# 09-IMC.net
KiCad netlist of a schematic drawn in Altium Designer
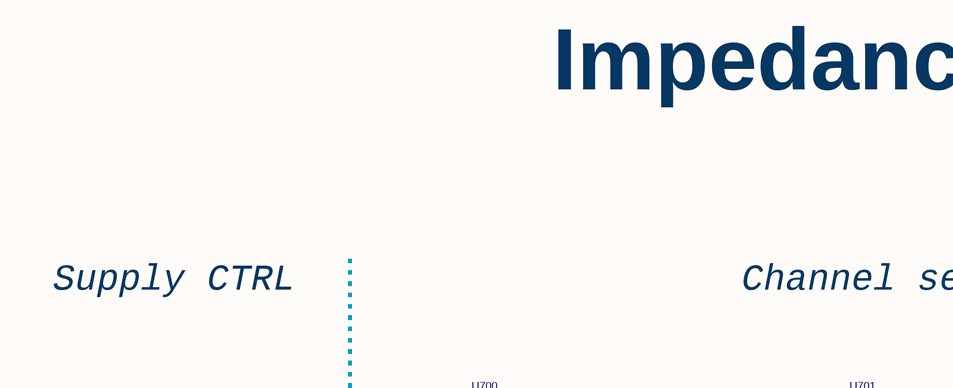
[diagram p0: 09-IMC.SchDoc, top left]
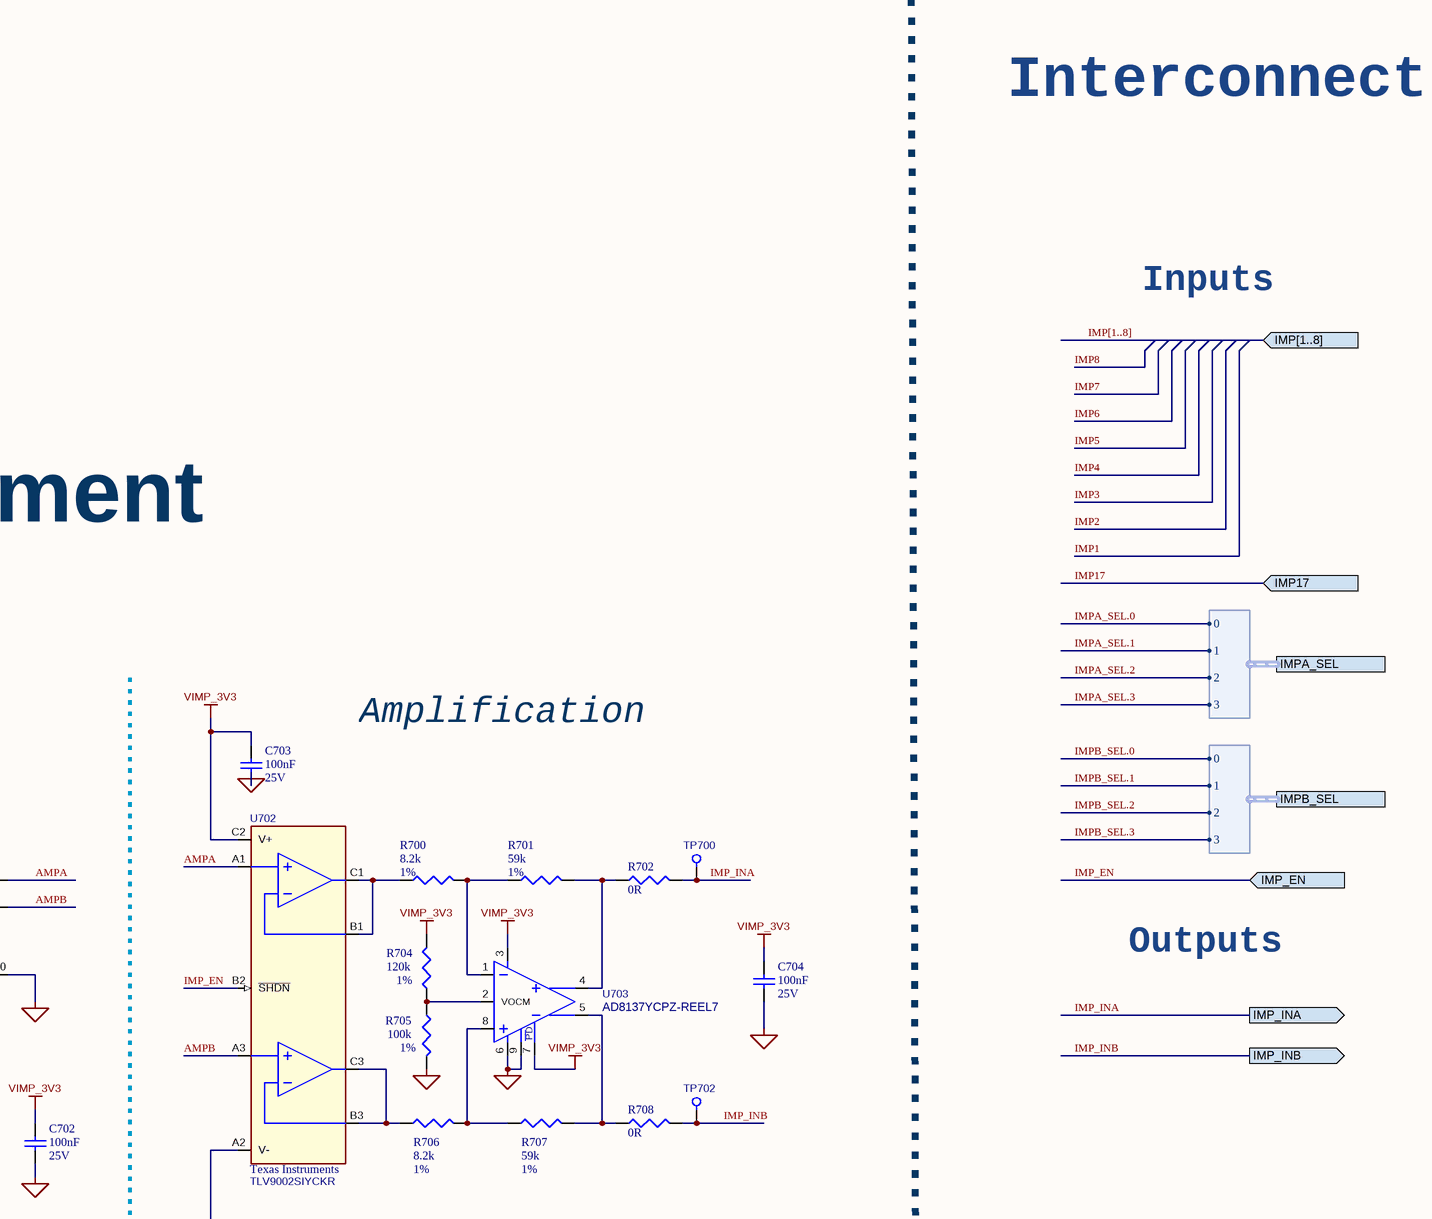
[diagram p1: 09-IMC.SchDoc, top right]
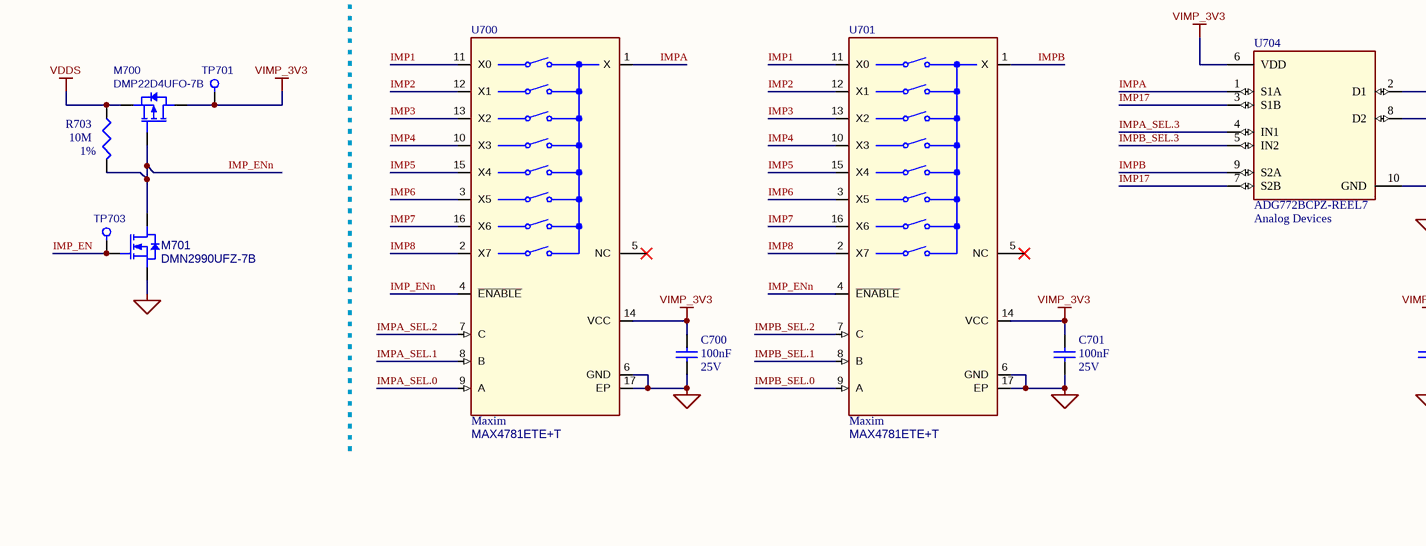
[diagram p2: 09-IMC.SchDoc, bottom left]
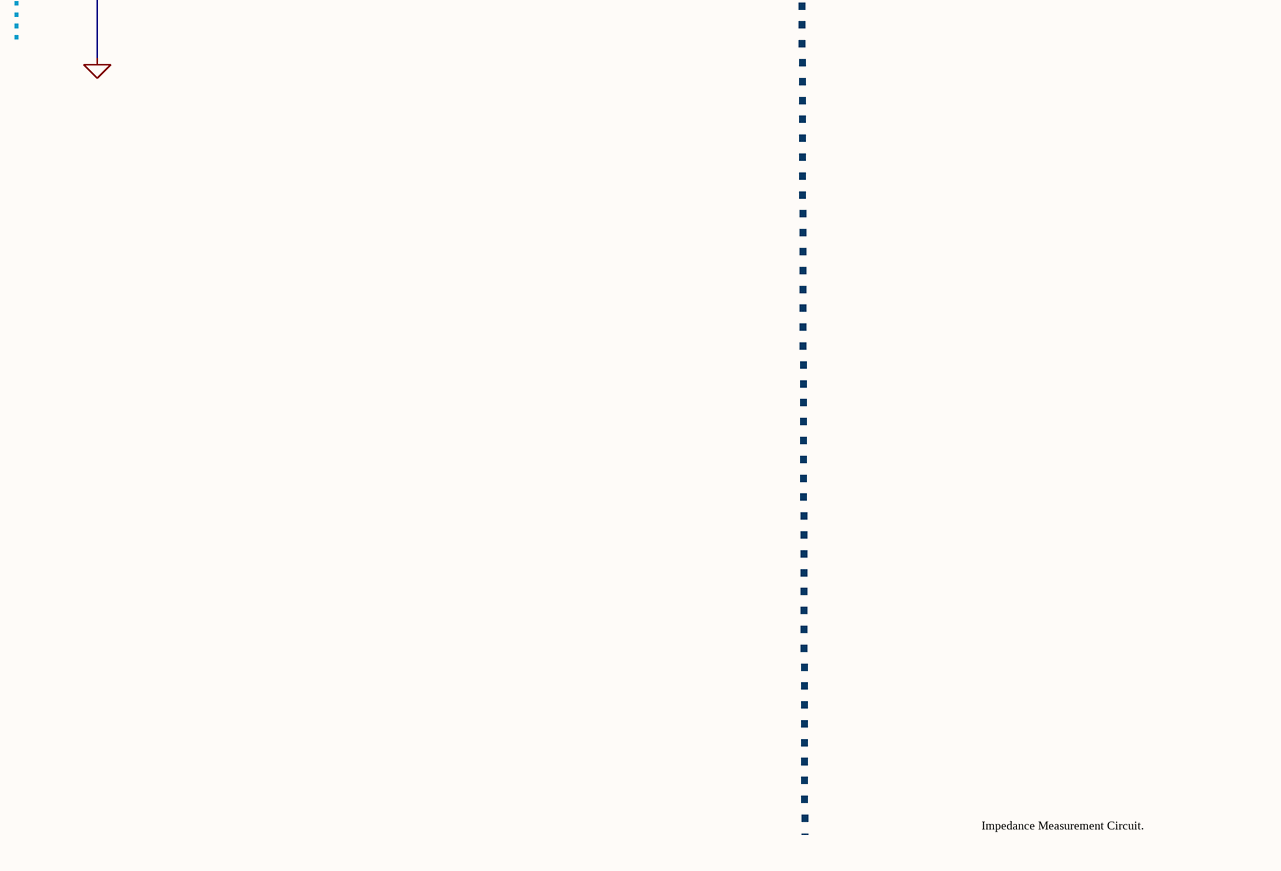
[diagram p3: 09-IMC.SchDoc, bottom right]

(export (version "E")
  (design (tool "Eeschema 10.0.6"))
  (components
    (comp (ref "C700")
      (value "100nF")
      (footprint "C0201_C")
      (fields
        (field (name "MANUFACTURER") "Murata")
        (field (name "MANUFACTURER PART NUMBER") "GRM033R61E104KE14J")
        (field (name "RATED DC VOLTAGE (URDC)") "25V")
      )
      (libsource (lib "MP-LIBRARY") (part "GRM033R61E104KE14J"))
    )
    (comp (ref "C701")
      (value "100nF")
      (footprint "C0201_C")
      (fields
        (field (name "MANUFACTURER") "Murata")
        (field (name "MANUFACTURER PART NUMBER") "GRM033R61E104KE14J")
        (field (name "RATED DC VOLTAGE (URDC)") "25V")
      )
      (libsource (lib "MP-LIBRARY") (part "GRM033R61E104KE14J"))
    )
    (comp (ref "C702")
      (value "100nF")
      (footprint "C0201_C")
      (fields
        (field (name "MANUFACTURER") "Murata")
        (field (name "MANUFACTURER PART NUMBER") "GRM033R61E104KE14J")
        (field (name "RATED DC VOLTAGE (URDC)") "25V")
      )
      (libsource (lib "MP-LIBRARY") (part "GRM033R61E104KE14J"))
    )
    (comp (ref "C703")
      (value "100nF")
      (footprint "C0201_C")
      (fields
        (field (name "MANUFACTURER") "Murata")
        (field (name "MANUFACTURER PART NUMBER") "GRM033R61E104KE14J")
        (field (name "RATED DC VOLTAGE (URDC)") "25V")
      )
      (libsource (lib "MP-LIBRARY") (part "GRM033R61E104KE14J"))
    )
    (comp (ref "C704")
      (value "100nF")
      (footprint "C0201_C")
      (fields
        (field (name "MANUFACTURER") "Murata")
        (field (name "MANUFACTURER PART NUMBER") "GRM033R61E104KE14J")
        (field (name "RATED DC VOLTAGE (URDC)") "25V")
      )
      (libsource (lib "MP-LIBRARY") (part "GRM033R61E104KE14J"))
    )
    (comp (ref "M700")
      (value "DMP22D4UFO-7B")
      (footprint "DIODESINC_X2-DFN0604-3")
      (description "MOSFET, P-chan, -20V, -383mA, DFN0604")
      (fields (field (name "MANUFACTURER") "Diodes Inc"))
      (libsource (lib "MP-LIBRARY") (part "DMP22D4UFO-7B"))
    )
    (comp (ref "M701")
      (value "DMN2990UFZ-7B")
      (footprint "DIODESINC_X2-DFN0606-3")
      (description "MOSFET, N-Chan, 20V, 170mA, DFN0606")
      (fields (field (name "MANUFACTURER") "Diodes Inc"))
      (libsource (lib "MP-LIBRARY") (part "DMN2990UFZ-7B"))
    )
    (comp (ref "R700")
      (value "8.2k")
      (footprint "R0201_C")
      (fields
        (field (name "MANUFACTURER") "Vishay")
        (field (name "MANUFACTURER PART NUMBER") "CRCW02018K20FNED")
        (field (name "TOLERANCE") "1%")
        (field (name "POWER") "50mW")
      )
      (libsource (lib "MP-LIBRARY") (part "CRCW02018K20FNED"))
    )
    (comp (ref "R701")
      (value "59k")
      (footprint "R0201_C")
      (fields
        (field (name "MANUFACTURER") "Vishay")
        (field (name "MANUFACTURER PART NUMBER") "CRCW020159K0FNED")
        (field (name "TOLERANCE") "1%")
        (field (name "POWER") "50mW")
      )
      (libsource (lib "MP-LIBRARY") (part "CRCW020159K0FNED"))
    )
    (comp (ref "R702")
      (value "0R")
      (footprint "R0201_C")
      (description "Fixed Resistor, Metal Glaze/thick Film, 0.05W, 0ohm, Surface Mount, 0201")
      (fields
        (field (name "MANUFACTURER") "Vishay")
        (field (name "MANUFACTURER PART NUMBER") "CRCW02010000Z0ED")
      )
      (libsource (lib "MP-LIBRARY") (part "CRCW02010000Z0ED"))
    )
    (comp (ref "R703")
      (value "10M")
      (footprint "R0201_C")
      (fields
        (field (name "MANUFACTURER") "Vishay Draloric")
        (field (name "MANUFACTURER PART NUMBER") "CRCW020110M0FNED")
        (field (name "TOLERANCE") "1%")
        (field (name "POWER") "50mW")
      )
      (libsource (lib "MP-LIBRARY") (part "CRCW020110M0FNED"))
    )
    (comp (ref "R704")
      (value "120k")
      (footprint "R0201_C")
      (fields
        (field (name "MANUFACTURER") "Vishay Dale")
        (field (name "MANUFACTURER PART NUMBER") "CRCW0201120KFNED")
        (field (name "TOLERANCE") "1%")
        (field (name "POWER") "50mW")
      )
      (libsource (lib "MP-LIBRARY") (part "CRCW0201120KFNED"))
    )
    (comp (ref "R705")
      (value "100k")
      (footprint "R0201_C")
      (fields
        (field (name "MANUFACTURER") "Vishay")
        (field (name "MANUFACTURER PART NUMBER") "CRCW0201100KFNED")
        (field (name "TOLERANCE") "1%")
        (field (name "POWER") "50mW")
      )
      (libsource (lib "MP-LIBRARY") (part "CRCW0201100KFNED"))
    )
    (comp (ref "R706")
      (value "8.2k")
      (footprint "R0201_C")
      (fields
        (field (name "MANUFACTURER") "Vishay")
        (field (name "MANUFACTURER PART NUMBER") "CRCW02018K20FNED")
        (field (name "TOLERANCE") "1%")
        (field (name "POWER") "50mW")
      )
      (libsource (lib "MP-LIBRARY") (part "CRCW02018K20FNED"))
    )
    (comp (ref "R707")
      (value "59k")
      (footprint "R0201_C")
      (fields
        (field (name "MANUFACTURER") "Vishay")
        (field (name "MANUFACTURER PART NUMBER") "CRCW020159K0FNED")
        (field (name "TOLERANCE") "1%")
        (field (name "POWER") "50mW")
      )
      (libsource (lib "MP-LIBRARY") (part "CRCW020159K0FNED"))
    )
    (comp (ref "R708")
      (value "0R")
      (footprint "R0201_C")
      (description "Fixed Resistor, Metal Glaze/thick Film, 0.05W, 0ohm, Surface Mount, 0201")
      (fields
        (field (name "MANUFACTURER") "Vishay")
        (field (name "MANUFACTURER PART NUMBER") "CRCW02010000Z0ED")
      )
      (libsource (lib "MP-LIBRARY") (part "CRCW02010000Z0ED"))
    )
    (comp (ref "TP700")
      (value "Test Point")
      (footprint "testpad_0.9mm")
      (description "Test pad, 0.90mm circular pad")
      (libsource (lib "MP-LIBRARY") (part "Test Point"))
    )
    (comp (ref "TP701")
      (value "Test Point")
      (footprint "testpad_0.9mm")
      (description "Test pad, 0.90mm circular pad")
      (libsource (lib "MP-LIBRARY") (part "Test Point"))
    )
    (comp (ref "TP702")
      (value "Test Point")
      (footprint "testpad_0.9mm")
      (description "Test pad, 0.90mm circular pad")
      (libsource (lib "MP-LIBRARY") (part "Test Point"))
    )
    (comp (ref "TP703")
      (value "Test Point")
      (footprint "testpad_0.9mm")
      (description "Test pad, 0.90mm circular pad")
      (libsource (lib "MP-LIBRARY") (part "Test Point"))
    )
    (comp (ref "U700")
      (value "MAX4781ETE+T")
      (footprint "MAXIM_21-0136")
      (description "Multiplexer, 8:1, 0.7 ohms, QFN-16")
      (fields (field (name "MANUFACTURER") "Maxim"))
      (libsource (lib "MP-LIBRARY") (part "MAX4781ETE+T"))
    )
    (comp (ref "U701")
      (value "MAX4781ETE+T")
      (footprint "MAXIM_21-0136")
      (description "Multiplexer, 8:1, 0.7 ohms, QFN-16")
      (fields (field (name "MANUFACTURER") "Maxim"))
      (libsource (lib "MP-LIBRARY") (part "MAX4781ETE+T"))
    )
    (comp (ref "U702")
      (value "TLV9002SIYCKR")
      (footprint "TI_YCK0009")
      (description "Op Amp, Dual, Rail-to-Rail, 1MHz, BGA-9")
      (fields (field (name "MANUFACTURER") "Texas Instruments"))
      (libsource (lib "MP-LIBRARY") (part "TLV9002SIYCKR_b"))
    )
    (comp (ref "U703")
      (value "AD8137YCPZ-REEL7")
      (footprint "AD_CP-8-13")
      (description "Differential Amplifier, 110 MHz, DFN-8")
      (fields (field (name "MANUFACTURER") "Analog Devices"))
      (libsource (lib "MP-LIBRARY") (part "AD8137YCPZ-REEL7"))
    )
    (comp (ref "U704")
      (value "ADG772BCPZ-REEL7")
      (footprint "10-Lead Mini LFCSP")
      (description "SPDT, 2 Func, 1 Channel, CMOS")
      (fields (field (name "MANUFACTURER") "Analog Devices"))
      (libsource (lib "MP-LIBRARY") (part "ADG772BCPZ-REEL7"))
    )
  )
  (nets
    (net (code "2") (name "/AMPA") (class "Default")
      (node (ref "U702") (pin "A1") (pinfunction "IN1+_A1") (pintype "passive"))
      (node (ref "U704") (pin "2") (pinfunction "D1_2") (pintype "bidirectional"))
    )
    (net (code "3") (name "/AMPB") (class "Default")
      (node (ref "U702") (pin "A3") (pinfunction "IN2+_A3") (pintype "passive"))
      (node (ref "U704") (pin "8") (pinfunction "D2_8") (pintype "bidirectional"))
    )
    (net (code "4") (name "/IMP1") (class "Default")
      (node (ref "U700") (pin "11") (pinfunction "X0_11") (pintype "passive"))
      (node (ref "U701") (pin "11") (pinfunction "X0_11") (pintype "passive"))
    )
    (net (code "5") (name "/IMP2") (class "Default")
      (node (ref "U700") (pin "12") (pinfunction "X1_12") (pintype "passive"))
      (node (ref "U701") (pin "12") (pinfunction "X1_12") (pintype "passive"))
    )
    (net (code "6") (name "/IMP3") (class "Default")
      (node (ref "U700") (pin "13") (pinfunction "X2_13") (pintype "passive"))
      (node (ref "U701") (pin "13") (pinfunction "X2_13") (pintype "passive"))
    )
    (net (code "7") (name "/IMP4") (class "Default")
      (node (ref "U700") (pin "10") (pinfunction "X3_10") (pintype "passive"))
      (node (ref "U701") (pin "10") (pinfunction "X3_10") (pintype "passive"))
    )
    (net (code "8") (name "/IMP5") (class "Default")
      (node (ref "U700") (pin "15") (pinfunction "X4_15") (pintype "passive"))
      (node (ref "U701") (pin "15") (pinfunction "X4_15") (pintype "passive"))
    )
    (net (code "9") (name "/IMP6") (class "Default")
      (node (ref "U700") (pin "3") (pinfunction "X5_3") (pintype "passive"))
      (node (ref "U701") (pin "3") (pinfunction "X5_3") (pintype "passive"))
    )
    (net (code "10") (name "/IMP7") (class "Default")
      (node (ref "U700") (pin "16") (pinfunction "X6_16") (pintype "passive"))
      (node (ref "U701") (pin "16") (pinfunction "X6_16") (pintype "passive"))
    )
    (net (code "11") (name "/IMP8") (class "Default")
      (node (ref "U700") (pin "2") (pinfunction "X7_2") (pintype "passive"))
      (node (ref "U701") (pin "2") (pinfunction "X7_2") (pintype "passive"))
    )
    (net (code "12") (name "/IMP17") (class "Default")
      (node (ref "U704") (pin "3") (pinfunction "S1B_3") (pintype "bidirectional"))
      (node (ref "U704") (pin "7") (pinfunction "S2B_7") (pintype "bidirectional"))
    )
    (net (code "13") (name "/IMPA") (class "Default")
      (node (ref "U700") (pin "1") (pinfunction "X_1") (pintype "passive"))
      (node (ref "U704") (pin "1") (pinfunction "S1A_1") (pintype "bidirectional"))
    )
    (net (code "14") (name "/IMPA_SEL.0") (class "Default")
      (node (ref "U700") (pin "9") (pinfunction "A_9") (pintype "input"))
    )
    (net (code "15") (name "/IMPA_SEL.1") (class "Default")
      (node (ref "U700") (pin "8") (pinfunction "B_8") (pintype "input"))
    )
    (net (code "16") (name "/IMPA_SEL.2") (class "Default")
      (node (ref "U700") (pin "7") (pinfunction "C_7") (pintype "input"))
    )
    (net (code "17") (name "/IMPA_SEL.3") (class "Default")
      (node (ref "U704") (pin "4") (pinfunction "IN1_4") (pintype "bidirectional"))
    )
    (net (code "18") (name "/IMPB") (class "Default")
      (node (ref "U701") (pin "1") (pinfunction "X_1") (pintype "passive"))
      (node (ref "U704") (pin "9") (pinfunction "S2A_9") (pintype "bidirectional"))
    )
    (net (code "19") (name "/IMPB_SEL.0") (class "Default")
      (node (ref "U701") (pin "9") (pinfunction "A_9") (pintype "input"))
    )
    (net (code "20") (name "/IMPB_SEL.1") (class "Default")
      (node (ref "U701") (pin "8") (pinfunction "B_8") (pintype "input"))
    )
    (net (code "21") (name "/IMPB_SEL.2") (class "Default")
      (node (ref "U701") (pin "7") (pinfunction "C_7") (pintype "input"))
    )
    (net (code "22") (name "/IMPB_SEL.3") (class "Default")
      (node (ref "U704") (pin "5") (pinfunction "IN2_5") (pintype "bidirectional"))
    )
    (net (code "24") (name "/IMP_EN") (class "Default")
      (node (ref "M701") (pin "1") (pinfunction "G_1") (pintype "passive"))
      (node (ref "TP703") (pin "1") (pinfunction "1_1") (pintype "passive"))
      (node (ref "U702") (pin "B2") (pinfunction "~{SHDN}_B2") (pintype "input"))
    )
    (net (code "25") (name "/IMP_ENn") (class "Default")
      (node (ref "M700") (pin "1") (pinfunction "G_1") (pintype "passive"))
      (node (ref "M701") (pin "3") (pinfunction "D_3") (pintype "passive"))
      (node (ref "R703") (pin "2") (pinfunction "2_2") (pintype "passive"))
      (node (ref "U700") (pin "4") (pinfunction "~{ENABLE}_4") (pintype "passive"))
      (node (ref "U701") (pin "4") (pinfunction "~{ENABLE}_4") (pintype "passive"))
    )
    (net (code "26") (name "/IMP_INA") (class "Default")
      (node (ref "R702") (pin "2") (pinfunction "2_2") (pintype "passive"))
      (node (ref "TP700") (pin "1") (pinfunction "1_1") (pintype "passive"))
    )
    (net (code "27") (name "/IMP_INB") (class "Default")
      (node (ref "R708") (pin "2") (pinfunction "2_2") (pintype "passive"))
      (node (ref "TP702") (pin "1") (pinfunction "1_1") (pintype "passive"))
    )
    (net (code "29") (name "GND") (class "Default")
      (node (ref "C700") (pin "1") (pinfunction "1_1") (pintype "passive"))
      (node (ref "C701") (pin "1") (pinfunction "1_1") (pintype "passive"))
      (node (ref "C702") (pin "1") (pinfunction "1_1") (pintype "passive"))
      (node (ref "C703") (pin "1") (pinfunction "1_1") (pintype "passive"))
      (node (ref "C704") (pin "1") (pinfunction "1_1") (pintype "passive"))
      (node (ref "M701") (pin "2") (pinfunction "S_2") (pintype "passive"))
      (node (ref "R705") (pin "2") (pinfunction "2_2") (pintype "passive"))
      (node (ref "U700") (pin "17") (pinfunction "EP_17") (pintype "passive"))
      (node (ref "U700") (pin "6") (pinfunction "GND_6") (pintype "passive"))
      (node (ref "U701") (pin "17") (pinfunction "EP_17") (pintype "passive"))
      (node (ref "U701") (pin "6") (pinfunction "GND_6") (pintype "passive"))
      (node (ref "U702") (pin "A2") (pinfunction "V-_A2") (pintype "power_in"))
      (node (ref "U703") (pin "6") (pinfunction "VS-_6") (pintype "power_in"))
      (node (ref "U703") (pin "9") (pinfunction "EP_9") (pintype "passive"))
      (node (ref "U704") (pin "10") (pinfunction "GND_10") (pintype "power_in"))
    )
    (net (code "30") (name "Net-(U702-IN1-)") (class "Default")
      (node (ref "R700") (pin "1") (pinfunction "1_1") (pintype "passive"))
      (node (ref "U702") (pin "B1") (pinfunction "IN1-_B1") (pintype "passive"))
      (node (ref "U702") (pin "C1") (pinfunction "OUT1_C1") (pintype "passive"))
    )
    (net (code "31") (name "Net-(U702-IN2-)") (class "Default")
      (node (ref "R706") (pin "1") (pinfunction "1_1") (pintype "passive"))
      (node (ref "U702") (pin "B3") (pinfunction "IN2-_B3") (pintype "passive"))
      (node (ref "U702") (pin "C3") (pinfunction "OUT2_C3") (pintype "passive"))
    )
    (net (code "32") (name "Net-(U703-+IN)") (class "Default")
      (node (ref "R706") (pin "2") (pinfunction "2_2") (pintype "passive"))
      (node (ref "R707") (pin "1") (pinfunction "1_1") (pintype "passive"))
      (node (ref "U703") (pin "8") (pinfunction "+IN_8") (pintype "passive"))
    )
    (net (code "33") (name "Net-(U703-+OUT)") (class "Default")
      (node (ref "R701") (pin "2") (pinfunction "2_2") (pintype "passive"))
      (node (ref "R702") (pin "1") (pinfunction "1_1") (pintype "passive"))
      (node (ref "U703") (pin "4") (pinfunction "+OUT_4") (pintype "passive"))
    )
    (net (code "34") (name "Net-(U703--IN)") (class "Default")
      (node (ref "R700") (pin "2") (pinfunction "2_2") (pintype "passive"))
      (node (ref "R701") (pin "1") (pinfunction "1_1") (pintype "passive"))
      (node (ref "U703") (pin "1") (pinfunction "-IN_1") (pintype "passive"))
    )
    (net (code "35") (name "Net-(U703--OUT)") (class "Default")
      (node (ref "R707") (pin "2") (pinfunction "2_2") (pintype "passive"))
      (node (ref "R708") (pin "1") (pinfunction "1_1") (pintype "passive"))
      (node (ref "U703") (pin "5") (pinfunction "-OUT_5") (pintype "passive"))
    )
    (net (code "36") (name "Net-(U703-VOCM)") (class "Default")
      (node (ref "R704") (pin "1") (pinfunction "1_1") (pintype "passive"))
      (node (ref "R705") (pin "1") (pinfunction "1_1") (pintype "passive"))
      (node (ref "U703") (pin "2") (pinfunction "VOCM_2") (pintype "passive"))
    )
    (net (code "37") (name "VDDS") (class "Default")
      (node (ref "M700") (pin "2") (pinfunction "S_2") (pintype "passive"))
      (node (ref "R703") (pin "1") (pinfunction "1_1") (pintype "passive"))
    )
    (net (code "38") (name "VIMP_3V3") (class "Default")
      (node (ref "C700") (pin "2") (pinfunction "2_2") (pintype "passive"))
      (node (ref "C701") (pin "2") (pinfunction "2_2") (pintype "passive"))
      (node (ref "C702") (pin "2") (pinfunction "2_2") (pintype "passive"))
      (node (ref "C703") (pin "2") (pinfunction "2_2") (pintype "passive"))
      (node (ref "C704") (pin "2") (pinfunction "2_2") (pintype "passive"))
      (node (ref "M700") (pin "3") (pinfunction "D_3") (pintype "passive"))
      (node (ref "R704") (pin "2") (pinfunction "2_2") (pintype "passive"))
      (node (ref "TP701") (pin "1") (pinfunction "1_1") (pintype "passive"))
      (node (ref "U700") (pin "14") (pinfunction "VCC_14") (pintype "power_in"))
      (node (ref "U701") (pin "14") (pinfunction "VCC_14") (pintype "power_in"))
      (node (ref "U702") (pin "C2") (pinfunction "V+_C2") (pintype "power_in"))
      (node (ref "U703") (pin "3") (pinfunction "VS+_3") (pintype "power_in"))
      (node (ref "U703") (pin "7") (pinfunction "~{PD}_7") (pintype "passive"))
      (node (ref "U704") (pin "6") (pinfunction "VDD_6") (pintype "power_in"))
    )
    (net (code "39") (name "unconnected-(U700-NC-Pad5)") (class "Default")
      (node (ref "U700") (pin "5") (pinfunction "NC_5") (pintype "passive+no_connect"))
    )
    (net (code "40") (name "unconnected-(U701-NC-Pad5)") (class "Default")
      (node (ref "U701") (pin "5") (pinfunction "NC_5") (pintype "passive+no_connect"))
    )
  )
)
